# neonred-live-schematic_2026-10-09.net
KiCad netlist of a schematic drawn in EasyEDA
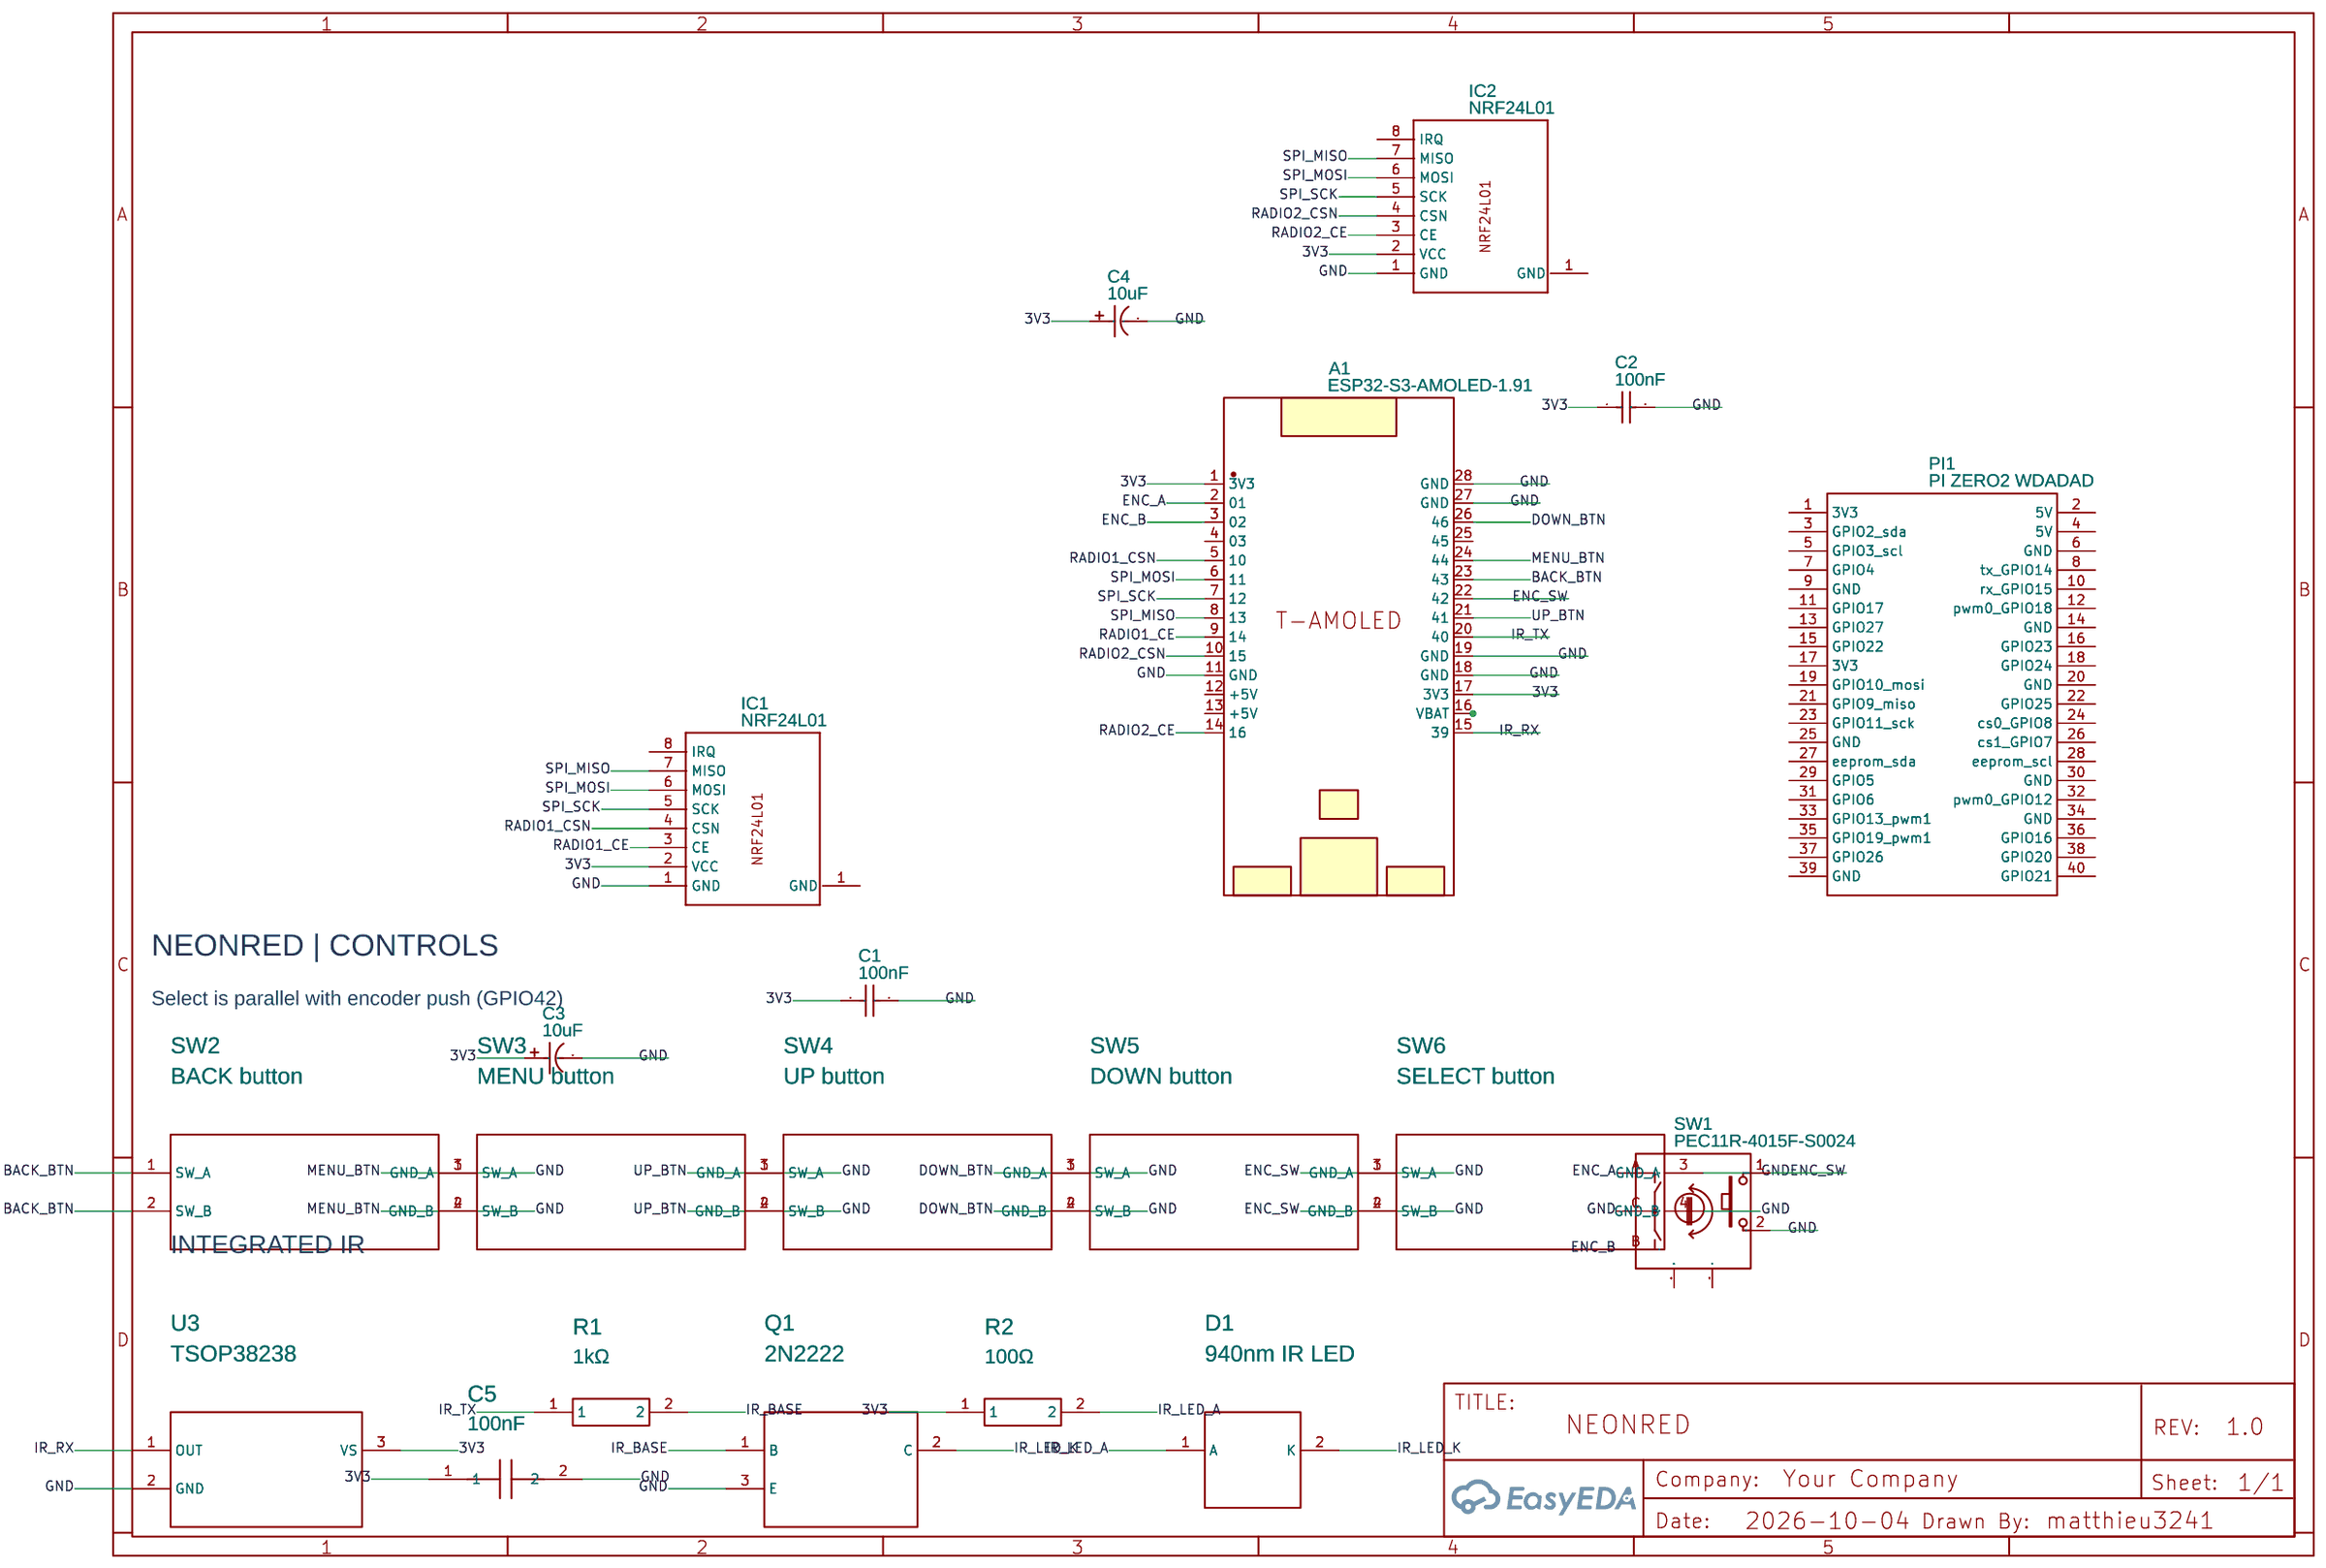
[diagram p0: schematic sheet]

(export (version "E")
  (design (tool "Eeschema 10.0.6"))
  (components
    (comp (ref "A1")
      (value "ESP32-S3-AMOLED-1.91")
      (fields (field (name "Manufacturer Part") "T-Display S3 AMOLED") (field (name "Manufacturer") "Lilygo"))
      (libsource (lib "") (part "ESP32-S3-AMOLED-1.91"))
    )
    (comp (ref "C1")
      (value "100nF")
      (fields (field (name "Manufacturer Part") "0.1UF(104) +-20% 63v"))
      (libsource (lib "") (part "100nF"))
    )
    (comp (ref "C2")
      (value "100nF")
      (fields (field (name "Manufacturer Part") "0.1UF(104) +-20% 63v"))
      (libsource (lib "") (part "100nF"))
    )
    (comp (ref "C3") (value "10uF") (libsource (lib "") (part "Capacitor 10uF TH")))
    (comp (ref "C4") (value "10uF") (libsource (lib "") (part "Capacitor 10uF TH")))
    (comp (ref "C5")
      (value "100nF")
      (fields (field (name "Manufacturer Part") "100nF ceramic THT"))
      (libsource (lib "") (part "100nF_1"))
    )
    (comp (ref "D1")
      (value "940nm IR LED")
      (fields (field (name "Manufacturer Part") "940nm IR LED, 5 mm THT"))
      (libsource (lib "") (part "940nm IR LED"))
    )
    (comp (ref "IC1") (value "NRF24L01") (libsource (lib "") (part "NRF24L01")))
    (comp (ref "IC2") (value "NRF24L01") (libsource (lib "") (part "NRF24L01")))
    (comp (ref "PI1") (value "PI ZERO2 WDADAD") (libsource (lib "") (part "PI ZERO2 WDADAD")))
    (comp (ref "Q1")
      (value "2N2222")
      (fields (field (name "Manufacturer Part") "2N2222A"))
      (libsource (lib "") (part "2N2222"))
    )
    (comp (ref "R1")
      (value "1kΩ")
      (fields (field (name "Manufacturer Part") "1k axial THT"))
      (libsource (lib "") (part "1kΩ"))
    )
    (comp (ref "R2")
      (value "100Ω")
      (fields (field (name "Manufacturer Part") "100Ω axial THT"))
      (libsource (lib "") (part "100Ω"))
    )
    (comp (ref "SW1")
      (value "PEC11R-4015F-S0024")
      (fields (field (name "Manufacturer") "BOURNS"))
      (libsource (lib "") (part "PEC11R-4015F-S0024"))
    )
    (comp (ref "SW2")
      (value "BACK button")
      (fields (field (name "Manufacturer Part") "6x6mm THT tactile switch, NO"))
      (libsource (lib "") (part "BACK button"))
    )
    (comp (ref "SW3")
      (value "MENU button")
      (fields (field (name "Manufacturer Part") "6x6mm THT tactile switch, NO"))
      (libsource (lib "") (part "MENU button"))
    )
    (comp (ref "SW4")
      (value "UP button")
      (fields (field (name "Manufacturer Part") "6x6mm THT tactile switch, NO"))
      (libsource (lib "") (part "UP button"))
    )
    (comp (ref "SW5")
      (value "DOWN button")
      (fields (field (name "Manufacturer Part") "6x6mm THT tactile switch, NO"))
      (libsource (lib "") (part "DOWN button"))
    )
    (comp (ref "SW6")
      (value "SELECT button")
      (fields (field (name "Manufacturer Part") "6x6mm THT tactile switch, NO"))
      (libsource (lib "") (part "SELECT button"))
    )
    (comp (ref "U3") (value "TSOP38238") (libsource (lib "") (part "TSOP38238")))
  )
  (nets
    (net (code "1") (name "/3V3") (class "Default")
      (node (ref "A1") (pin "1") (pinfunction "3V3_1") (pintype "unspecified"))
      (node (ref "A1") (pin "17") (pinfunction "3V3_17") (pintype "unspecified"))
      (node (ref "C1") (pin "1") (pinfunction "1_1") (pintype "input"))
      (node (ref "C2") (pin "1") (pinfunction "1_1") (pintype "input"))
      (node (ref "C3") (pin "1") (pinfunction "1_1") (pintype "input"))
      (node (ref "C4") (pin "1") (pinfunction "1_1") (pintype "input"))
      (node (ref "C5") (pin "1") (pinfunction "1_1") (pintype "unspecified"))
      (node (ref "IC1") (pin "2") (pinfunction "VCC_2") (pintype "bidirectional"))
      (node (ref "IC2") (pin "2") (pinfunction "VCC_2") (pintype "bidirectional"))
      (node (ref "R2") (pin "1") (pinfunction "1_1") (pintype "unspecified"))
      (node (ref "U3") (pin "3") (pinfunction "VS_3") (pintype "unspecified"))
    )
    (net (code "2") (name "/BACK_BTN") (class "Default")
      (node (ref "A1") (pin "23") (pinfunction "43_23") (pintype "unspecified"))
      (node (ref "SW2") (pin "1") (pinfunction "SW_A_1") (pintype "unspecified"))
      (node (ref "SW2") (pin "2") (pinfunction "SW_B_2") (pintype "unspecified"))
    )
    (net (code "3") (name "/DOWN_BTN") (class "Default")
      (node (ref "A1") (pin "26") (pinfunction "46_26") (pintype "unspecified"))
      (node (ref "SW5") (pin "1") (pinfunction "SW_A_1") (pintype "unspecified"))
      (node (ref "SW5") (pin "2") (pinfunction "SW_B_2") (pintype "unspecified"))
    )
    (net (code "4") (name "/ENC_A") (class "Default")
      (node (ref "A1") (pin "2") (pinfunction "01_2") (pintype "unspecified"))
      (node (ref "SW1") (pin "A") (pinfunction "A_A") (pintype "unspecified"))
    )
    (net (code "5") (name "/ENC_B") (class "Default")
      (node (ref "A1") (pin "3") (pinfunction "02_3") (pintype "unspecified"))
      (node (ref "SW1") (pin "B") (pinfunction "B_B") (pintype "unspecified"))
    )
    (net (code "6") (name "/ENC_SW") (class "Default")
      (node (ref "A1") (pin "22") (pinfunction "42_22") (pintype "unspecified"))
      (node (ref "SW1") (pin "1") (pinfunction "1_1") (pintype "unspecified"))
      (node (ref "SW6") (pin "1") (pinfunction "SW_A_1") (pintype "unspecified"))
      (node (ref "SW6") (pin "2") (pinfunction "SW_B_2") (pintype "unspecified"))
    )
    (net (code "7") (name "/GND") (class "Default")
      (node (ref "A1") (pin "11") (pinfunction "GND_11") (pintype "unspecified"))
      (node (ref "A1") (pin "18") (pinfunction "GND_18") (pintype "unspecified"))
      (node (ref "A1") (pin "19") (pinfunction "GND_19") (pintype "unspecified"))
      (node (ref "A1") (pin "27") (pinfunction "GND_27") (pintype "unspecified"))
      (node (ref "A1") (pin "28") (pinfunction "GND_28") (pintype "unspecified"))
      (node (ref "C1") (pin "2") (pinfunction "2_2") (pintype "input"))
      (node (ref "C2") (pin "2") (pinfunction "2_2") (pintype "input"))
      (node (ref "C3") (pin "2") (pinfunction "2_2") (pintype "input"))
      (node (ref "C4") (pin "2") (pinfunction "2_2") (pintype "input"))
      (node (ref "C5") (pin "2") (pinfunction "2_2") (pintype "unspecified"))
      (node (ref "IC1") (pin "1") (pinfunction "GND_1") (pintype "bidirectional"))
      (node (ref "IC2") (pin "1") (pinfunction "GND_1") (pintype "bidirectional"))
      (node (ref "Q1") (pin "3") (pinfunction "E_3") (pintype "unspecified"))
      (node (ref "SW1") (pin "2") (pinfunction "2_2") (pintype "unspecified"))
      (node (ref "SW1") (pin "C") (pinfunction "C_C") (pintype "unspecified"))
      (node (ref "SW2") (pin "3") (pinfunction "GND_A_3") (pintype "unspecified"))
      (node (ref "SW2") (pin "4") (pinfunction "GND_B_4") (pintype "unspecified"))
      (node (ref "SW3") (pin "3") (pinfunction "GND_A_3") (pintype "unspecified"))
      (node (ref "SW3") (pin "4") (pinfunction "GND_B_4") (pintype "unspecified"))
      (node (ref "SW4") (pin "3") (pinfunction "GND_A_3") (pintype "unspecified"))
      (node (ref "SW4") (pin "4") (pinfunction "GND_B_4") (pintype "unspecified"))
      (node (ref "SW5") (pin "3") (pinfunction "GND_A_3") (pintype "unspecified"))
      (node (ref "SW5") (pin "4") (pinfunction "GND_B_4") (pintype "unspecified"))
      (node (ref "SW6") (pin "3") (pinfunction "GND_A_3") (pintype "unspecified"))
      (node (ref "SW6") (pin "4") (pinfunction "GND_B_4") (pintype "unspecified"))
      (node (ref "U3") (pin "2") (pinfunction "GND_2") (pintype "unspecified"))
    )
    (net (code "8") (name "/IR_BASE") (class "Default")
      (node (ref "Q1") (pin "1") (pinfunction "B_1") (pintype "unspecified"))
      (node (ref "R1") (pin "2") (pinfunction "2_2") (pintype "unspecified"))
    )
    (net (code "9") (name "/IR_LED_A") (class "Default")
      (node (ref "D1") (pin "1") (pinfunction "A_1") (pintype "unspecified"))
      (node (ref "R2") (pin "2") (pinfunction "2_2") (pintype "unspecified"))
    )
    (net (code "10") (name "/IR_LED_K") (class "Default")
      (node (ref "D1") (pin "2") (pinfunction "K_2") (pintype "unspecified"))
      (node (ref "Q1") (pin "2") (pinfunction "C_2") (pintype "unspecified"))
    )
    (net (code "11") (name "/IR_RX") (class "Default")
      (node (ref "A1") (pin "15") (pinfunction "39_15") (pintype "unspecified"))
      (node (ref "U3") (pin "1") (pinfunction "OUT_1") (pintype "unspecified"))
    )
    (net (code "12") (name "/IR_TX") (class "Default")
      (node (ref "A1") (pin "20") (pinfunction "40_20") (pintype "unspecified"))
      (node (ref "R1") (pin "1") (pinfunction "1_1") (pintype "unspecified"))
    )
    (net (code "13") (name "/MENU_BTN") (class "Default")
      (node (ref "A1") (pin "24") (pinfunction "44_24") (pintype "unspecified"))
      (node (ref "SW3") (pin "1") (pinfunction "SW_A_1") (pintype "unspecified"))
      (node (ref "SW3") (pin "2") (pinfunction "SW_B_2") (pintype "unspecified"))
    )
    (net (code "14") (name "/RADIO1_CE") (class "Default")
      (node (ref "A1") (pin "9") (pinfunction "14_9") (pintype "unspecified"))
      (node (ref "IC1") (pin "3") (pinfunction "CE_3") (pintype "bidirectional"))
    )
    (net (code "15") (name "/RADIO1_CSN") (class "Default")
      (node (ref "A1") (pin "5") (pinfunction "10_5") (pintype "unspecified"))
      (node (ref "IC1") (pin "4") (pinfunction "CSN_4") (pintype "bidirectional"))
    )
    (net (code "16") (name "/RADIO2_CE") (class "Default")
      (node (ref "A1") (pin "14") (pinfunction "16_14") (pintype "unspecified"))
      (node (ref "IC2") (pin "3") (pinfunction "CE_3") (pintype "bidirectional"))
    )
    (net (code "17") (name "/RADIO2_CSN") (class "Default")
      (node (ref "A1") (pin "10") (pinfunction "15_10") (pintype "unspecified"))
      (node (ref "IC2") (pin "4") (pinfunction "CSN_4") (pintype "bidirectional"))
    )
    (net (code "18") (name "/SPI_MISO") (class "Default")
      (node (ref "A1") (pin "8") (pinfunction "13_8") (pintype "unspecified"))
      (node (ref "IC1") (pin "7") (pinfunction "MISO_7") (pintype "bidirectional"))
      (node (ref "IC2") (pin "7") (pinfunction "MISO_7") (pintype "bidirectional"))
    )
    (net (code "19") (name "/SPI_MOSI") (class "Default")
      (node (ref "A1") (pin "6") (pinfunction "11_6") (pintype "unspecified"))
      (node (ref "IC1") (pin "6") (pinfunction "MOSI_6") (pintype "bidirectional"))
      (node (ref "IC2") (pin "6") (pinfunction "MOSI_6") (pintype "bidirectional"))
    )
    (net (code "20") (name "/SPI_SCK") (class "Default")
      (node (ref "A1") (pin "7") (pinfunction "12_7") (pintype "unspecified"))
      (node (ref "IC1") (pin "5") (pinfunction "SCK_5") (pintype "bidirectional"))
      (node (ref "IC2") (pin "5") (pinfunction "SCK_5") (pintype "bidirectional"))
    )
    (net (code "21") (name "/UP_BTN") (class "Default")
      (node (ref "A1") (pin "21") (pinfunction "41_21") (pintype "unspecified"))
      (node (ref "SW4") (pin "1") (pinfunction "SW_A_1") (pintype "unspecified"))
      (node (ref "SW4") (pin "2") (pinfunction "SW_B_2") (pintype "unspecified"))
    )
    (net (code "22") (name "unconnected-(A1-+5V-Pad12)") (class "Default")
      (node (ref "A1") (pin "12") (pinfunction "+5V_12") (pintype "unspecified"))
    )
    (net (code "23") (name "unconnected-(A1-+5V-Pad13)") (class "Default")
      (node (ref "A1") (pin "13") (pinfunction "+5V_13") (pintype "unspecified"))
    )
    (net (code "24") (name "unconnected-(A1-03-Pad4)") (class "Default")
      (node (ref "A1") (pin "4") (pinfunction "03_4") (pintype "unspecified"))
    )
    (net (code "25") (name "unconnected-(A1-45-Pad25)") (class "Default")
      (node (ref "A1") (pin "25") (pinfunction "45_25") (pintype "unspecified"))
    )
    (net (code "26") (name "unconnected-(A1-VBAT-Pad16)") (class "Default")
      (node (ref "A1") (pin "16") (pinfunction "VBAT_16") (pintype "unspecified"))
    )
    (net (code "27") (name "unconnected-(IC1-GND-Pad1)") (class "Default")
      (node (ref "IC1") (pin "1") (pinfunction "GND_1") (pintype "bidirectional"))
    )
    (net (code "28") (name "unconnected-(IC1-IRQ-Pad8)") (class "Default")
      (node (ref "IC1") (pin "8") (pinfunction "IRQ_8") (pintype "bidirectional"))
    )
    (net (code "29") (name "unconnected-(IC2-GND-Pad1)") (class "Default")
      (node (ref "IC2") (pin "1") (pinfunction "GND_1") (pintype "bidirectional"))
    )
    (net (code "30") (name "unconnected-(IC2-IRQ-Pad8)") (class "Default")
      (node (ref "IC2") (pin "8") (pinfunction "IRQ_8") (pintype "bidirectional"))
    )
    (net (code "31") (name "unconnected-(PI1-3V3-Pad1)") (class "Default")
      (node (ref "PI1") (pin "1") (pinfunction "3V3_1") (pintype "unspecified"))
    )
    (net (code "32") (name "unconnected-(PI1-3V3-Pad17)") (class "Default")
      (node (ref "PI1") (pin "17") (pinfunction "3V3_17") (pintype "unspecified"))
    )
    (net (code "33") (name "unconnected-(PI1-5V-Pad2)") (class "Default")
      (node (ref "PI1") (pin "2") (pinfunction "5V_2") (pintype "unspecified"))
    )
    (net (code "34") (name "unconnected-(PI1-5V-Pad4)") (class "Default")
      (node (ref "PI1") (pin "4") (pinfunction "5V_4") (pintype "unspecified"))
    )
    (net (code "35") (name "unconnected-(PI1-GND-Pad6)") (class "Default")
      (node (ref "PI1") (pin "6") (pinfunction "GND_6") (pintype "unspecified"))
    )
    (net (code "36") (name "unconnected-(PI1-GND-Pad9)") (class "Default")
      (node (ref "PI1") (pin "9") (pinfunction "GND_9") (pintype "unspecified"))
    )
    (net (code "37") (name "unconnected-(PI1-GND-Pad14)") (class "Default")
      (node (ref "PI1") (pin "14") (pinfunction "GND_14") (pintype "unspecified"))
    )
    (net (code "38") (name "unconnected-(PI1-GND-Pad20)") (class "Default")
      (node (ref "PI1") (pin "20") (pinfunction "GND_20") (pintype "unspecified"))
    )
    (net (code "39") (name "unconnected-(PI1-GND-Pad25)") (class "Default")
      (node (ref "PI1") (pin "25") (pinfunction "GND_25") (pintype "unspecified"))
    )
    (net (code "40") (name "unconnected-(PI1-GND-Pad30)") (class "Default")
      (node (ref "PI1") (pin "30") (pinfunction "GND_30") (pintype "unspecified"))
    )
    (net (code "41") (name "unconnected-(PI1-GND-Pad34)") (class "Default")
      (node (ref "PI1") (pin "34") (pinfunction "GND_34") (pintype "unspecified"))
    )
    (net (code "42") (name "unconnected-(PI1-GND-Pad39)") (class "Default")
      (node (ref "PI1") (pin "39") (pinfunction "GND_39") (pintype "unspecified"))
    )
    (net (code "43") (name "unconnected-(PI1-GPIO2_sda-Pad3)") (class "Default")
      (node (ref "PI1") (pin "3") (pinfunction "GPIO2_sda_3") (pintype "unspecified"))
    )
    (net (code "44") (name "unconnected-(PI1-GPIO3_scl-Pad5)") (class "Default")
      (node (ref "PI1") (pin "5") (pinfunction "GPIO3_scl_5") (pintype "unspecified"))
    )
    (net (code "45") (name "unconnected-(PI1-GPIO4-Pad7)") (class "Default")
      (node (ref "PI1") (pin "7") (pinfunction "GPIO4_7") (pintype "unspecified"))
    )
    (net (code "46") (name "unconnected-(PI1-GPIO5-Pad29)") (class "Default")
      (node (ref "PI1") (pin "29") (pinfunction "GPIO5_29") (pintype "unspecified"))
    )
    (net (code "47") (name "unconnected-(PI1-GPIO6-Pad31)") (class "Default")
      (node (ref "PI1") (pin "31") (pinfunction "GPIO6_31") (pintype "unspecified"))
    )
    (net (code "48") (name "unconnected-(PI1-GPIO9_miso-Pad21)") (class "Default")
      (node (ref "PI1") (pin "21") (pinfunction "GPIO9_miso_21") (pintype "unspecified"))
    )
    (net (code "49") (name "unconnected-(PI1-GPIO10_mosi-Pad19)") (class "Default")
      (node (ref "PI1") (pin "19") (pinfunction "GPIO10_mosi_19") (pintype "unspecified"))
    )
    (net (code "50") (name "unconnected-(PI1-GPIO11_sck-Pad23)") (class "Default")
      (node (ref "PI1") (pin "23") (pinfunction "GPIO11_sck_23") (pintype "unspecified"))
    )
    (net (code "51") (name "unconnected-(PI1-GPIO13_pwm1-Pad33)") (class "Default")
      (node (ref "PI1") (pin "33") (pinfunction "GPIO13_pwm1_33") (pintype "unspecified"))
    )
    (net (code "52") (name "unconnected-(PI1-GPIO16-Pad36)") (class "Default")
      (node (ref "PI1") (pin "36") (pinfunction "GPIO16_36") (pintype "unspecified"))
    )
    (net (code "53") (name "unconnected-(PI1-GPIO17-Pad11)") (class "Default")
      (node (ref "PI1") (pin "11") (pinfunction "GPIO17_11") (pintype "unspecified"))
    )
    (net (code "54") (name "unconnected-(PI1-GPIO19_pwm1-Pad35)") (class "Default")
      (node (ref "PI1") (pin "35") (pinfunction "GPIO19_pwm1_35") (pintype "unspecified"))
    )
    (net (code "55") (name "unconnected-(PI1-GPIO20-Pad38)") (class "Default")
      (node (ref "PI1") (pin "38") (pinfunction "GPIO20_38") (pintype "unspecified"))
    )
    (net (code "56") (name "unconnected-(PI1-GPIO21-Pad40)") (class "Default")
      (node (ref "PI1") (pin "40") (pinfunction "GPIO21_40") (pintype "unspecified"))
    )
    (net (code "57") (name "unconnected-(PI1-GPIO22-Pad15)") (class "Default")
      (node (ref "PI1") (pin "15") (pinfunction "GPIO22_15") (pintype "unspecified"))
    )
    (net (code "58") (name "unconnected-(PI1-GPIO23-Pad16)") (class "Default")
      (node (ref "PI1") (pin "16") (pinfunction "GPIO23_16") (pintype "unspecified"))
    )
    (net (code "59") (name "unconnected-(PI1-GPIO24-Pad18)") (class "Default")
      (node (ref "PI1") (pin "18") (pinfunction "GPIO24_18") (pintype "unspecified"))
    )
    (net (code "60") (name "unconnected-(PI1-GPIO25-Pad22)") (class "Default")
      (node (ref "PI1") (pin "22") (pinfunction "GPIO25_22") (pintype "unspecified"))
    )
    (net (code "61") (name "unconnected-(PI1-GPIO26-Pad37)") (class "Default")
      (node (ref "PI1") (pin "37") (pinfunction "GPIO26_37") (pintype "unspecified"))
    )
    (net (code "62") (name "unconnected-(PI1-GPIO27-Pad13)") (class "Default")
      (node (ref "PI1") (pin "13") (pinfunction "GPIO27_13") (pintype "unspecified"))
    )
    (net (code "63") (name "unconnected-(PI1-cs0_GPIO8-Pad24)") (class "Default")
      (node (ref "PI1") (pin "24") (pinfunction "cs0_GPIO8_24") (pintype "unspecified"))
    )
    (net (code "64") (name "unconnected-(PI1-cs1_GPIO7-Pad26)") (class "Default")
      (node (ref "PI1") (pin "26") (pinfunction "cs1_GPIO7_26") (pintype "unspecified"))
    )
    (net (code "65") (name "unconnected-(PI1-eeprom_scl-Pad28)") (class "Default")
      (node (ref "PI1") (pin "28") (pinfunction "eeprom_scl_28") (pintype "unspecified"))
    )
    (net (code "66") (name "unconnected-(PI1-eeprom_sda-Pad27)") (class "Default")
      (node (ref "PI1") (pin "27") (pinfunction "eeprom_sda_27") (pintype "unspecified"))
    )
    (net (code "67") (name "unconnected-(PI1-pwm0_GPIO12-Pad32)") (class "Default")
      (node (ref "PI1") (pin "32") (pinfunction "pwm0_GPIO12_32") (pintype "unspecified"))
    )
    (net (code "68") (name "unconnected-(PI1-pwm0_GPIO18-Pad12)") (class "Default")
      (node (ref "PI1") (pin "12") (pinfunction "pwm0_GPIO18_12") (pintype "unspecified"))
    )
    (net (code "69") (name "unconnected-(PI1-rx_GPIO15-Pad10)") (class "Default")
      (node (ref "PI1") (pin "10") (pinfunction "rx_GPIO15_10") (pintype "unspecified"))
    )
    (net (code "70") (name "unconnected-(PI1-tx_GPIO14-Pad8)") (class "Default")
      (node (ref "PI1") (pin "8") (pinfunction "tx_GPIO14_8") (pintype "unspecified"))
    )
    (net (code "71") (name "unconnected-(SW1-PadMT1)") (class "Default")
      (node (ref "SW1") (pin "MT1") (pinfunction "MT1_MT1") (pintype "unspecified"))
    )
    (net (code "72") (name "unconnected-(SW1-PadMT2)") (class "Default")
      (node (ref "SW1") (pin "MT2") (pinfunction "MT2_MT2") (pintype "unspecified"))
    )
  )
)
